# M2k_Breadboard_r1.net
KiCad netlist of a schematic drawn in EAGLE
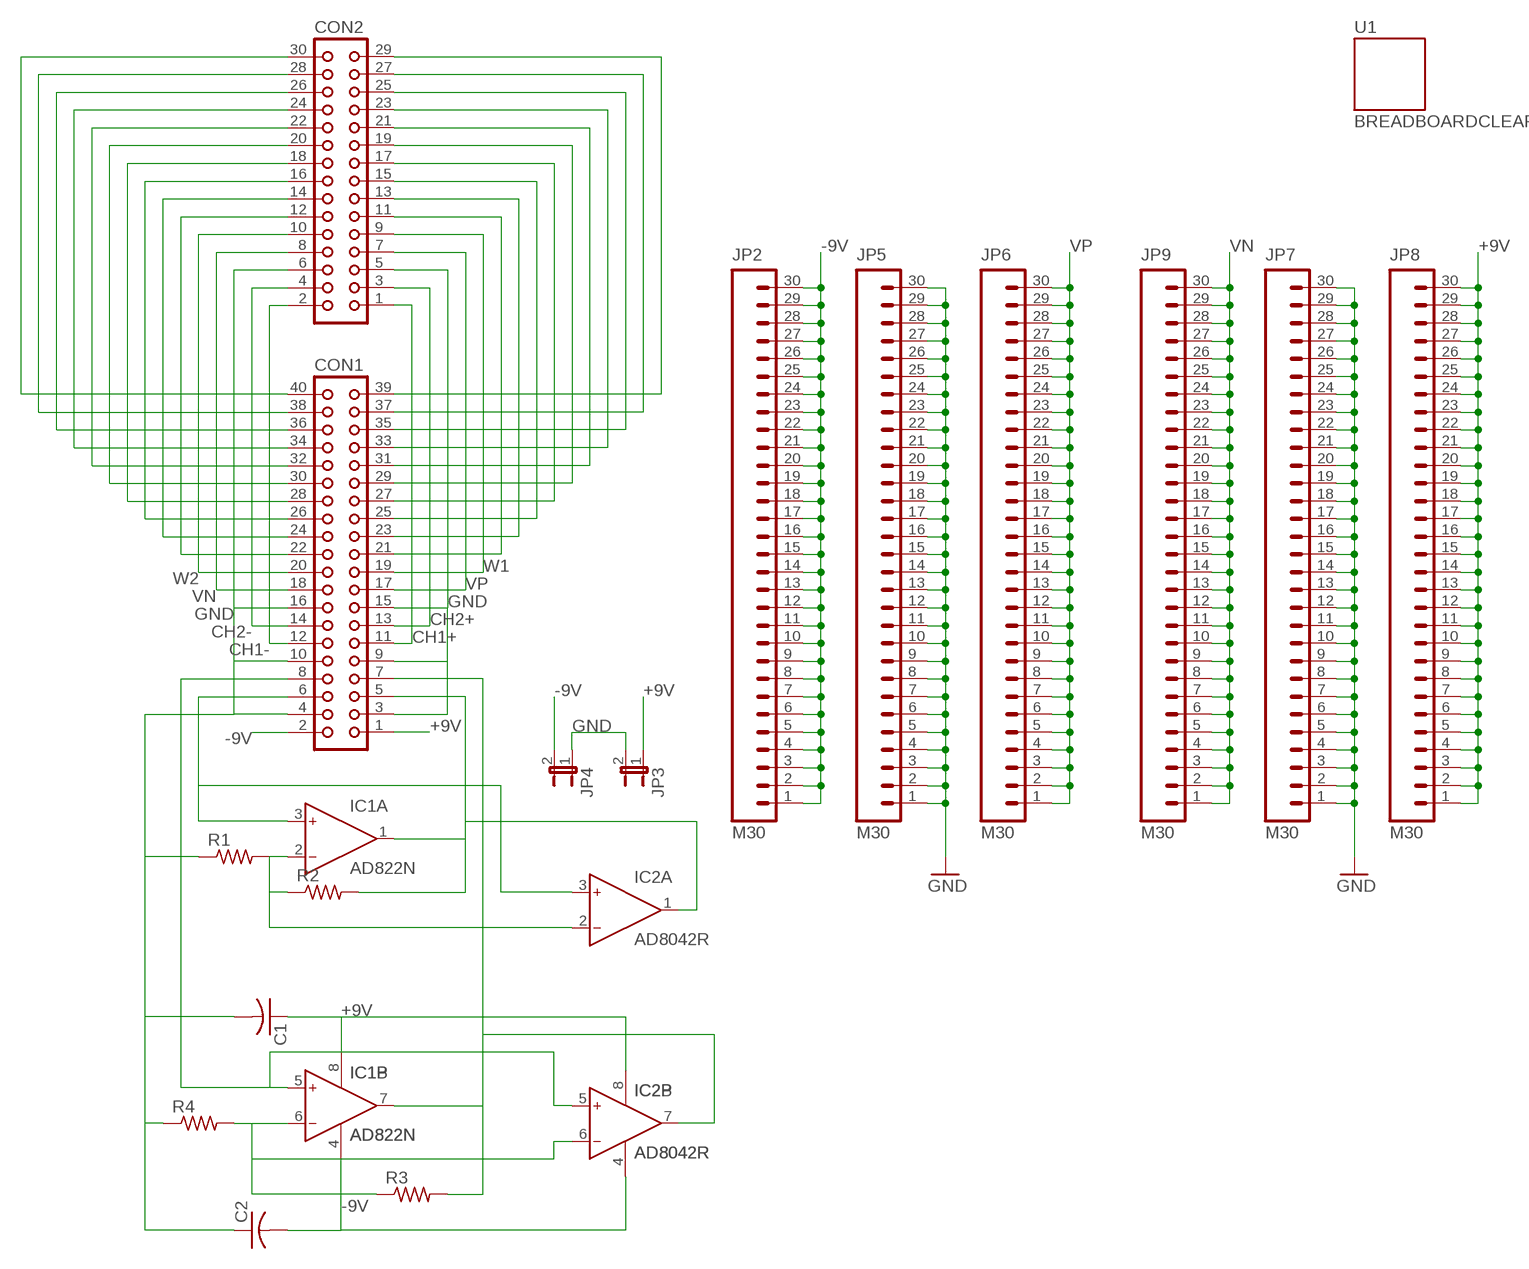
[diagram p0: schematic, sheet 1]

(export (version "E")
  (design (tool "Eeschema 10.0.6"))
  (components
    (comp (ref "C1")
      (value "C-US050-024X044")
      (footprint "eagle-import:C050-024X044")
      (libsource (lib "eagle-import") (part "C-US050-024X044"))
    )
    (comp (ref "C2")
      (value "C-US050-024X044")
      (footprint "eagle-import:C050-024X044")
      (libsource (lib "eagle-import") (part "C-US050-024X044"))
    )
    (comp (ref "CON1")
      (value "CON40")
      (footprint "eagle-import:CON40")
      (libsource (lib "eagle-import") (part "CON40"))
    )
    (comp (ref "CON2")
      (value "CON34")
      (footprint "eagle-import:CON34")
      (libsource (lib "eagle-import") (part "CON34"))
    )
    (comp (ref "IC1")
      (value "AD822N")
      (footprint "eagle-import:DIL08")
      (libsource (lib "eagle-import") (part "AD822N"))
    )
    (comp (ref "IC2")
      (value "AD8042R")
      (footprint "eagle-import:SO8")
      (fields (field (name "MF") "ALTERA CORPORATION") (field (name "MPN") "AD8042AR"))
      (libsource (lib "eagle-import") (part "AD8042R"))
    )
    (comp (ref "JP2")
      (value "M30")
      (footprint "eagle-import:1X30")
      (libsource (lib "eagle-import") (part "M30"))
    )
    (comp (ref "JP3")
      (value "JP1E")
      (footprint "eagle-import:JP1")
      (libsource (lib "eagle-import") (part "JP1E"))
    )
    (comp (ref "JP4")
      (value "JP1E")
      (footprint "eagle-import:JP1")
      (libsource (lib "eagle-import") (part "JP1E"))
    )
    (comp (ref "JP5")
      (value "M30")
      (footprint "eagle-import:1X30")
      (libsource (lib "eagle-import") (part "M30"))
    )
    (comp (ref "JP6")
      (value "M30")
      (footprint "eagle-import:1X30")
      (libsource (lib "eagle-import") (part "M30"))
    )
    (comp (ref "JP7")
      (value "M30")
      (footprint "eagle-import:1X30")
      (libsource (lib "eagle-import") (part "M30"))
    )
    (comp (ref "JP8")
      (value "M30")
      (footprint "eagle-import:1X30")
      (libsource (lib "eagle-import") (part "M30"))
    )
    (comp (ref "JP9")
      (value "M30")
      (footprint "eagle-import:1X30")
      (libsource (lib "eagle-import") (part "M30"))
    )
    (comp (ref "R1")
      (value "R-US_0207/7")
      (footprint "eagle-import:0207_7")
      (libsource (lib "eagle-import") (part "R-US_0207/7"))
    )
    (comp (ref "R2")
      (value "R-US_0207/7")
      (footprint "eagle-import:0207_7")
      (libsource (lib "eagle-import") (part "R-US_0207/7"))
    )
    (comp (ref "R3")
      (value "R-US_0207/7")
      (footprint "eagle-import:0207_7")
      (libsource (lib "eagle-import") (part "R-US_0207/7"))
    )
    (comp (ref "R4")
      (value "R-US_0207/7")
      (footprint "eagle-import:0207_7")
      (libsource (lib "eagle-import") (part "R-US_0207/7"))
    )
    (comp (ref "U1")
      (value "BREADBOARDCLEAR")
      (footprint "eagle-import:BREADBOARD_CLEAR")
      (libsource (lib "eagle-import") (part "BREADBOARDCLEAR"))
    )
  )
  (nets
    (net (code "1") (name "/+9V") (class "Default")
      (node (ref "C1") (pin "1") (pinfunction "1_1") (pintype "passive"))
      (node (ref "CON1") (pin "1") (pinfunction "1_1") (pintype "passive"))
      (node (ref "IC1") (pin "8") (pinfunction "V+_8") (pintype "power_in"))
      (node (ref "IC2") (pin "8") (pinfunction "V+_8") (pintype "power_in"))
      (node (ref "JP3") (pin "1") (pinfunction "1_1") (pintype "passive"))
      (node (ref "JP8") (pin "1") (pinfunction "1_1") (pintype "passive"))
      (node (ref "JP8") (pin "10") (pinfunction "10_10") (pintype "passive"))
      (node (ref "JP8") (pin "11") (pinfunction "11_11") (pintype "passive"))
      (node (ref "JP8") (pin "12") (pinfunction "12_12") (pintype "passive"))
      (node (ref "JP8") (pin "13") (pinfunction "13_13") (pintype "passive"))
      (node (ref "JP8") (pin "14") (pinfunction "14_14") (pintype "passive"))
      (node (ref "JP8") (pin "15") (pinfunction "15_15") (pintype "passive"))
      (node (ref "JP8") (pin "16") (pinfunction "16_16") (pintype "passive"))
      (node (ref "JP8") (pin "17") (pinfunction "17_17") (pintype "passive"))
      (node (ref "JP8") (pin "18") (pinfunction "18_18") (pintype "passive"))
      (node (ref "JP8") (pin "19") (pinfunction "19_19") (pintype "passive"))
      (node (ref "JP8") (pin "2") (pinfunction "2_2") (pintype "passive"))
      (node (ref "JP8") (pin "20") (pinfunction "20_20") (pintype "passive"))
      (node (ref "JP8") (pin "21") (pinfunction "21_21") (pintype "passive"))
      (node (ref "JP8") (pin "22") (pinfunction "22_22") (pintype "passive"))
      (node (ref "JP8") (pin "23") (pinfunction "23_23") (pintype "passive"))
      (node (ref "JP8") (pin "24") (pinfunction "24_24") (pintype "passive"))
      (node (ref "JP8") (pin "25") (pinfunction "25_25") (pintype "passive"))
      (node (ref "JP8") (pin "26") (pinfunction "26_26") (pintype "passive"))
      (node (ref "JP8") (pin "27") (pinfunction "27_27") (pintype "passive"))
      (node (ref "JP8") (pin "28") (pinfunction "28_28") (pintype "passive"))
      (node (ref "JP8") (pin "29") (pinfunction "29_29") (pintype "passive"))
      (node (ref "JP8") (pin "3") (pinfunction "3_3") (pintype "passive"))
      (node (ref "JP8") (pin "30") (pinfunction "30_30") (pintype "passive"))
      (node (ref "JP8") (pin "4") (pinfunction "4_4") (pintype "passive"))
      (node (ref "JP8") (pin "5") (pinfunction "5_5") (pintype "passive"))
      (node (ref "JP8") (pin "6") (pinfunction "6_6") (pintype "passive"))
      (node (ref "JP8") (pin "7") (pinfunction "7_7") (pintype "passive"))
      (node (ref "JP8") (pin "8") (pinfunction "8_8") (pintype "passive"))
      (node (ref "JP8") (pin "9") (pinfunction "9_9") (pintype "passive"))
    )
    (net (code "2") (name "/-9V") (class "Default")
      (node (ref "C2") (pin "2") (pinfunction "2_2") (pintype "passive"))
      (node (ref "CON1") (pin "2") (pinfunction "2_2") (pintype "passive"))
      (node (ref "IC1") (pin "4") (pinfunction "V-_4") (pintype "power_in"))
      (node (ref "IC2") (pin "4") (pinfunction "V-_4") (pintype "power_in"))
      (node (ref "JP2") (pin "1") (pinfunction "1_1") (pintype "passive"))
      (node (ref "JP2") (pin "10") (pinfunction "10_10") (pintype "passive"))
      (node (ref "JP2") (pin "11") (pinfunction "11_11") (pintype "passive"))
      (node (ref "JP2") (pin "12") (pinfunction "12_12") (pintype "passive"))
      (node (ref "JP2") (pin "13") (pinfunction "13_13") (pintype "passive"))
      (node (ref "JP2") (pin "14") (pinfunction "14_14") (pintype "passive"))
      (node (ref "JP2") (pin "15") (pinfunction "15_15") (pintype "passive"))
      (node (ref "JP2") (pin "16") (pinfunction "16_16") (pintype "passive"))
      (node (ref "JP2") (pin "17") (pinfunction "17_17") (pintype "passive"))
      (node (ref "JP2") (pin "18") (pinfunction "18_18") (pintype "passive"))
      (node (ref "JP2") (pin "19") (pinfunction "19_19") (pintype "passive"))
      (node (ref "JP2") (pin "2") (pinfunction "2_2") (pintype "passive"))
      (node (ref "JP2") (pin "20") (pinfunction "20_20") (pintype "passive"))
      (node (ref "JP2") (pin "21") (pinfunction "21_21") (pintype "passive"))
      (node (ref "JP2") (pin "22") (pinfunction "22_22") (pintype "passive"))
      (node (ref "JP2") (pin "23") (pinfunction "23_23") (pintype "passive"))
      (node (ref "JP2") (pin "24") (pinfunction "24_24") (pintype "passive"))
      (node (ref "JP2") (pin "25") (pinfunction "25_25") (pintype "passive"))
      (node (ref "JP2") (pin "26") (pinfunction "26_26") (pintype "passive"))
      (node (ref "JP2") (pin "27") (pinfunction "27_27") (pintype "passive"))
      (node (ref "JP2") (pin "28") (pinfunction "28_28") (pintype "passive"))
      (node (ref "JP2") (pin "29") (pinfunction "29_29") (pintype "passive"))
      (node (ref "JP2") (pin "3") (pinfunction "3_3") (pintype "passive"))
      (node (ref "JP2") (pin "30") (pinfunction "30_30") (pintype "passive"))
      (node (ref "JP2") (pin "4") (pinfunction "4_4") (pintype "passive"))
      (node (ref "JP2") (pin "5") (pinfunction "5_5") (pintype "passive"))
      (node (ref "JP2") (pin "6") (pinfunction "6_6") (pintype "passive"))
      (node (ref "JP2") (pin "7") (pinfunction "7_7") (pintype "passive"))
      (node (ref "JP2") (pin "8") (pinfunction "8_8") (pintype "passive"))
      (node (ref "JP2") (pin "9") (pinfunction "9_9") (pintype "passive"))
      (node (ref "JP4") (pin "2") (pinfunction "2_2") (pintype "passive"))
    )
    (net (code "3") (name "/CH1+") (class "Default")
      (node (ref "CON1") (pin "11") (pinfunction "11_11") (pintype "passive"))
      (node (ref "CON2") (pin "1") (pinfunction "1_1") (pintype "passive"))
    )
    (net (code "4") (name "/CH1-") (class "Default")
      (node (ref "CON1") (pin "12") (pinfunction "12_12") (pintype "passive"))
      (node (ref "CON2") (pin "2") (pinfunction "2_2") (pintype "passive"))
    )
    (net (code "5") (name "/CH2+") (class "Default")
      (node (ref "CON1") (pin "13") (pinfunction "13_13") (pintype "passive"))
      (node (ref "CON2") (pin "3") (pinfunction "3_3") (pintype "passive"))
    )
    (net (code "6") (name "/CH2-") (class "Default")
      (node (ref "CON1") (pin "14") (pinfunction "14_14") (pintype "passive"))
      (node (ref "CON2") (pin "4") (pinfunction "4_4") (pintype "passive"))
    )
    (net (code "7") (name "/VN") (class "Default")
      (node (ref "CON1") (pin "18") (pinfunction "18_18") (pintype "passive"))
      (node (ref "CON2") (pin "8") (pinfunction "8_8") (pintype "passive"))
      (node (ref "JP9") (pin "1") (pinfunction "1_1") (pintype "passive"))
      (node (ref "JP9") (pin "10") (pinfunction "10_10") (pintype "passive"))
      (node (ref "JP9") (pin "11") (pinfunction "11_11") (pintype "passive"))
      (node (ref "JP9") (pin "12") (pinfunction "12_12") (pintype "passive"))
      (node (ref "JP9") (pin "13") (pinfunction "13_13") (pintype "passive"))
      (node (ref "JP9") (pin "14") (pinfunction "14_14") (pintype "passive"))
      (node (ref "JP9") (pin "15") (pinfunction "15_15") (pintype "passive"))
      (node (ref "JP9") (pin "16") (pinfunction "16_16") (pintype "passive"))
      (node (ref "JP9") (pin "17") (pinfunction "17_17") (pintype "passive"))
      (node (ref "JP9") (pin "18") (pinfunction "18_18") (pintype "passive"))
      (node (ref "JP9") (pin "19") (pinfunction "19_19") (pintype "passive"))
      (node (ref "JP9") (pin "2") (pinfunction "2_2") (pintype "passive"))
      (node (ref "JP9") (pin "20") (pinfunction "20_20") (pintype "passive"))
      (node (ref "JP9") (pin "21") (pinfunction "21_21") (pintype "passive"))
      (node (ref "JP9") (pin "22") (pinfunction "22_22") (pintype "passive"))
      (node (ref "JP9") (pin "23") (pinfunction "23_23") (pintype "passive"))
      (node (ref "JP9") (pin "24") (pinfunction "24_24") (pintype "passive"))
      (node (ref "JP9") (pin "25") (pinfunction "25_25") (pintype "passive"))
      (node (ref "JP9") (pin "26") (pinfunction "26_26") (pintype "passive"))
      (node (ref "JP9") (pin "27") (pinfunction "27_27") (pintype "passive"))
      (node (ref "JP9") (pin "28") (pinfunction "28_28") (pintype "passive"))
      (node (ref "JP9") (pin "29") (pinfunction "29_29") (pintype "passive"))
      (node (ref "JP9") (pin "3") (pinfunction "3_3") (pintype "passive"))
      (node (ref "JP9") (pin "30") (pinfunction "30_30") (pintype "passive"))
      (node (ref "JP9") (pin "4") (pinfunction "4_4") (pintype "passive"))
      (node (ref "JP9") (pin "5") (pinfunction "5_5") (pintype "passive"))
      (node (ref "JP9") (pin "6") (pinfunction "6_6") (pintype "passive"))
      (node (ref "JP9") (pin "7") (pinfunction "7_7") (pintype "passive"))
      (node (ref "JP9") (pin "8") (pinfunction "8_8") (pintype "passive"))
      (node (ref "JP9") (pin "9") (pinfunction "9_9") (pintype "passive"))
    )
    (net (code "8") (name "/VP") (class "Default")
      (node (ref "CON1") (pin "17") (pinfunction "17_17") (pintype "passive"))
      (node (ref "CON2") (pin "7") (pinfunction "7_7") (pintype "passive"))
      (node (ref "JP6") (pin "1") (pinfunction "1_1") (pintype "passive"))
      (node (ref "JP6") (pin "10") (pinfunction "10_10") (pintype "passive"))
      (node (ref "JP6") (pin "11") (pinfunction "11_11") (pintype "passive"))
      (node (ref "JP6") (pin "12") (pinfunction "12_12") (pintype "passive"))
      (node (ref "JP6") (pin "13") (pinfunction "13_13") (pintype "passive"))
      (node (ref "JP6") (pin "14") (pinfunction "14_14") (pintype "passive"))
      (node (ref "JP6") (pin "15") (pinfunction "15_15") (pintype "passive"))
      (node (ref "JP6") (pin "16") (pinfunction "16_16") (pintype "passive"))
      (node (ref "JP6") (pin "17") (pinfunction "17_17") (pintype "passive"))
      (node (ref "JP6") (pin "18") (pinfunction "18_18") (pintype "passive"))
      (node (ref "JP6") (pin "19") (pinfunction "19_19") (pintype "passive"))
      (node (ref "JP6") (pin "2") (pinfunction "2_2") (pintype "passive"))
      (node (ref "JP6") (pin "20") (pinfunction "20_20") (pintype "passive"))
      (node (ref "JP6") (pin "21") (pinfunction "21_21") (pintype "passive"))
      (node (ref "JP6") (pin "22") (pinfunction "22_22") (pintype "passive"))
      (node (ref "JP6") (pin "23") (pinfunction "23_23") (pintype "passive"))
      (node (ref "JP6") (pin "24") (pinfunction "24_24") (pintype "passive"))
      (node (ref "JP6") (pin "25") (pinfunction "25_25") (pintype "passive"))
      (node (ref "JP6") (pin "26") (pinfunction "26_26") (pintype "passive"))
      (node (ref "JP6") (pin "27") (pinfunction "27_27") (pintype "passive"))
      (node (ref "JP6") (pin "28") (pinfunction "28_28") (pintype "passive"))
      (node (ref "JP6") (pin "29") (pinfunction "29_29") (pintype "passive"))
      (node (ref "JP6") (pin "3") (pinfunction "3_3") (pintype "passive"))
      (node (ref "JP6") (pin "30") (pinfunction "30_30") (pintype "passive"))
      (node (ref "JP6") (pin "4") (pinfunction "4_4") (pintype "passive"))
      (node (ref "JP6") (pin "5") (pinfunction "5_5") (pintype "passive"))
      (node (ref "JP6") (pin "6") (pinfunction "6_6") (pintype "passive"))
      (node (ref "JP6") (pin "7") (pinfunction "7_7") (pintype "passive"))
      (node (ref "JP6") (pin "8") (pinfunction "8_8") (pintype "passive"))
      (node (ref "JP6") (pin "9") (pinfunction "9_9") (pintype "passive"))
    )
    (net (code "9") (name "/W1") (class "Default")
      (node (ref "CON1") (pin "19") (pinfunction "19_19") (pintype "passive"))
      (node (ref "CON2") (pin "9") (pinfunction "9_9") (pintype "passive"))
    )
    (net (code "10") (name "/W2") (class "Default")
      (node (ref "CON1") (pin "20") (pinfunction "20_20") (pintype "passive"))
      (node (ref "CON2") (pin "10") (pinfunction "10_10") (pintype "passive"))
    )
    (net (code "11") (name "GND") (class "Default")
      (node (ref "C1") (pin "2") (pinfunction "2_2") (pintype "passive"))
      (node (ref "C2") (pin "1") (pinfunction "1_1") (pintype "passive"))
      (node (ref "CON1") (pin "10") (pinfunction "10_10") (pintype "passive"))
      (node (ref "CON1") (pin "15") (pinfunction "15_15") (pintype "passive"))
      (node (ref "CON1") (pin "16") (pinfunction "16_16") (pintype "passive"))
      (node (ref "CON1") (pin "3") (pinfunction "3_3") (pintype "passive"))
      (node (ref "CON1") (pin "4") (pinfunction "4_4") (pintype "passive"))
      (node (ref "CON1") (pin "9") (pinfunction "9_9") (pintype "passive"))
      (node (ref "CON2") (pin "5") (pinfunction "5_5") (pintype "passive"))
      (node (ref "CON2") (pin "6") (pinfunction "6_6") (pintype "passive"))
      (node (ref "JP3") (pin "2") (pinfunction "2_2") (pintype "passive"))
      (node (ref "JP4") (pin "1") (pinfunction "1_1") (pintype "passive"))
      (node (ref "JP5") (pin "1") (pinfunction "1_1") (pintype "passive"))
      (node (ref "JP5") (pin "10") (pinfunction "10_10") (pintype "passive"))
      (node (ref "JP5") (pin "11") (pinfunction "11_11") (pintype "passive"))
      (node (ref "JP5") (pin "12") (pinfunction "12_12") (pintype "passive"))
      (node (ref "JP5") (pin "13") (pinfunction "13_13") (pintype "passive"))
      (node (ref "JP5") (pin "14") (pinfunction "14_14") (pintype "passive"))
      (node (ref "JP5") (pin "15") (pinfunction "15_15") (pintype "passive"))
      (node (ref "JP5") (pin "16") (pinfunction "16_16") (pintype "passive"))
      (node (ref "JP5") (pin "17") (pinfunction "17_17") (pintype "passive"))
      (node (ref "JP5") (pin "18") (pinfunction "18_18") (pintype "passive"))
      (node (ref "JP5") (pin "19") (pinfunction "19_19") (pintype "passive"))
      (node (ref "JP5") (pin "2") (pinfunction "2_2") (pintype "passive"))
      (node (ref "JP5") (pin "20") (pinfunction "20_20") (pintype "passive"))
      (node (ref "JP5") (pin "21") (pinfunction "21_21") (pintype "passive"))
      (node (ref "JP5") (pin "22") (pinfunction "22_22") (pintype "passive"))
      (node (ref "JP5") (pin "23") (pinfunction "23_23") (pintype "passive"))
      (node (ref "JP5") (pin "24") (pinfunction "24_24") (pintype "passive"))
      (node (ref "JP5") (pin "25") (pinfunction "25_25") (pintype "passive"))
      (node (ref "JP5") (pin "26") (pinfunction "26_26") (pintype "passive"))
      (node (ref "JP5") (pin "27") (pinfunction "27_27") (pintype "passive"))
      (node (ref "JP5") (pin "28") (pinfunction "28_28") (pintype "passive"))
      (node (ref "JP5") (pin "29") (pinfunction "29_29") (pintype "passive"))
      (node (ref "JP5") (pin "3") (pinfunction "3_3") (pintype "passive"))
      (node (ref "JP5") (pin "30") (pinfunction "30_30") (pintype "passive"))
      (node (ref "JP5") (pin "4") (pinfunction "4_4") (pintype "passive"))
      (node (ref "JP5") (pin "5") (pinfunction "5_5") (pintype "passive"))
      (node (ref "JP5") (pin "6") (pinfunction "6_6") (pintype "passive"))
      (node (ref "JP5") (pin "7") (pinfunction "7_7") (pintype "passive"))
      (node (ref "JP5") (pin "8") (pinfunction "8_8") (pintype "passive"))
      (node (ref "JP5") (pin "9") (pinfunction "9_9") (pintype "passive"))
      (node (ref "JP7") (pin "1") (pinfunction "1_1") (pintype "passive"))
      (node (ref "JP7") (pin "10") (pinfunction "10_10") (pintype "passive"))
      (node (ref "JP7") (pin "11") (pinfunction "11_11") (pintype "passive"))
      (node (ref "JP7") (pin "12") (pinfunction "12_12") (pintype "passive"))
      (node (ref "JP7") (pin "13") (pinfunction "13_13") (pintype "passive"))
      (node (ref "JP7") (pin "14") (pinfunction "14_14") (pintype "passive"))
      (node (ref "JP7") (pin "15") (pinfunction "15_15") (pintype "passive"))
      (node (ref "JP7") (pin "16") (pinfunction "16_16") (pintype "passive"))
      (node (ref "JP7") (pin "17") (pinfunction "17_17") (pintype "passive"))
      (node (ref "JP7") (pin "18") (pinfunction "18_18") (pintype "passive"))
      (node (ref "JP7") (pin "19") (pinfunction "19_19") (pintype "passive"))
      (node (ref "JP7") (pin "2") (pinfunction "2_2") (pintype "passive"))
      (node (ref "JP7") (pin "20") (pinfunction "20_20") (pintype "passive"))
      (node (ref "JP7") (pin "21") (pinfunction "21_21") (pintype "passive"))
      (node (ref "JP7") (pin "22") (pinfunction "22_22") (pintype "passive"))
      (node (ref "JP7") (pin "23") (pinfunction "23_23") (pintype "passive"))
      (node (ref "JP7") (pin "24") (pinfunction "24_24") (pintype "passive"))
      (node (ref "JP7") (pin "25") (pinfunction "25_25") (pintype "passive"))
      (node (ref "JP7") (pin "26") (pinfunction "26_26") (pintype "passive"))
      (node (ref "JP7") (pin "27") (pinfunction "27_27") (pintype "passive"))
      (node (ref "JP7") (pin "28") (pinfunction "28_28") (pintype "passive"))
      (node (ref "JP7") (pin "29") (pinfunction "29_29") (pintype "passive"))
      (node (ref "JP7") (pin "3") (pinfunction "3_3") (pintype "passive"))
      (node (ref "JP7") (pin "30") (pinfunction "30_30") (pintype "passive"))
      (node (ref "JP7") (pin "4") (pinfunction "4_4") (pintype "passive"))
      (node (ref "JP7") (pin "5") (pinfunction "5_5") (pintype "passive"))
      (node (ref "JP7") (pin "6") (pinfunction "6_6") (pintype "passive"))
      (node (ref "JP7") (pin "7") (pinfunction "7_7") (pintype "passive"))
      (node (ref "JP7") (pin "8") (pinfunction "8_8") (pintype "passive"))
      (node (ref "JP7") (pin "9") (pinfunction "9_9") (pintype "passive"))
      (node (ref "R1") (pin "1") (pinfunction "1_1") (pintype "passive"))
      (node (ref "R4") (pin "1") (pinfunction "1_1") (pintype "passive"))
    )
    (net (code "12") (name "Net-(CON1-Pad21)") (class "Default")
      (node (ref "CON1") (pin "21") (pinfunction "21_21") (pintype "passive"))
      (node (ref "CON2") (pin "11") (pinfunction "11_11") (pintype "passive"))
    )
    (net (code "13") (name "Net-(CON1-Pad22)") (class "Default")
      (node (ref "CON1") (pin "22") (pinfunction "22_22") (pintype "passive"))
      (node (ref "CON2") (pin "12") (pinfunction "12_12") (pintype "passive"))
    )
    (net (code "14") (name "Net-(CON1-Pad23)") (class "Default")
      (node (ref "CON1") (pin "23") (pinfunction "23_23") (pintype "passive"))
      (node (ref "CON2") (pin "13") (pinfunction "13_13") (pintype "passive"))
    )
    (net (code "15") (name "Net-(CON1-Pad24)") (class "Default")
      (node (ref "CON1") (pin "24") (pinfunction "24_24") (pintype "passive"))
      (node (ref "CON2") (pin "14") (pinfunction "14_14") (pintype "passive"))
    )
    (net (code "16") (name "Net-(CON1-Pad25)") (class "Default")
      (node (ref "CON1") (pin "25") (pinfunction "25_25") (pintype "passive"))
      (node (ref "CON2") (pin "15") (pinfunction "15_15") (pintype "passive"))
    )
    (net (code "17") (name "Net-(CON1-Pad26)") (class "Default")
      (node (ref "CON1") (pin "26") (pinfunction "26_26") (pintype "passive"))
      (node (ref "CON2") (pin "16") (pinfunction "16_16") (pintype "passive"))
    )
    (net (code "18") (name "Net-(CON1-Pad27)") (class "Default")
      (node (ref "CON1") (pin "27") (pinfunction "27_27") (pintype "passive"))
      (node (ref "CON2") (pin "17") (pinfunction "17_17") (pintype "passive"))
    )
    (net (code "19") (name "Net-(CON1-Pad28)") (class "Default")
      (node (ref "CON1") (pin "28") (pinfunction "28_28") (pintype "passive"))
      (node (ref "CON2") (pin "18") (pinfunction "18_18") (pintype "passive"))
    )
    (net (code "20") (name "Net-(CON1-Pad29)") (class "Default")
      (node (ref "CON1") (pin "29") (pinfunction "29_29") (pintype "passive"))
      (node (ref "CON2") (pin "19") (pinfunction "19_19") (pintype "passive"))
    )
    (net (code "21") (name "Net-(CON1-Pad30)") (class "Default")
      (node (ref "CON1") (pin "30") (pinfunction "30_30") (pintype "passive"))
      (node (ref "CON2") (pin "20") (pinfunction "20_20") (pintype "passive"))
    )
    (net (code "22") (name "Net-(CON1-Pad31)") (class "Default")
      (node (ref "CON1") (pin "31") (pinfunction "31_31") (pintype "passive"))
      (node (ref "CON2") (pin "21") (pinfunction "21_21") (pintype "passive"))
    )
    (net (code "23") (name "Net-(CON1-Pad32)") (class "Default")
      (node (ref "CON1") (pin "32") (pinfunction "32_32") (pintype "passive"))
      (node (ref "CON2") (pin "22") (pinfunction "22_22") (pintype "passive"))
    )
    (net (code "24") (name "Net-(CON1-Pad33)") (class "Default")
      (node (ref "CON1") (pin "33") (pinfunction "33_33") (pintype "passive"))
      (node (ref "CON2") (pin "23") (pinfunction "23_23") (pintype "passive"))
    )
    (net (code "25") (name "Net-(CON1-Pad34)") (class "Default")
      (node (ref "CON1") (pin "34") (pinfunction "34_34") (pintype "passive"))
      (node (ref "CON2") (pin "24") (pinfunction "24_24") (pintype "passive"))
    )
    (net (code "26") (name "Net-(CON1-Pad35)") (class "Default")
      (node (ref "CON1") (pin "35") (pinfunction "35_35") (pintype "passive"))
      (node (ref "CON2") (pin "25") (pinfunction "25_25") (pintype "passive"))
    )
    (net (code "27") (name "Net-(CON1-Pad36)") (class "Default")
      (node (ref "CON1") (pin "36") (pinfunction "36_36") (pintype "passive"))
      (node (ref "CON2") (pin "26") (pinfunction "26_26") (pintype "passive"))
    )
    (net (code "28") (name "Net-(CON1-Pad37)") (class "Default")
      (node (ref "CON1") (pin "37") (pinfunction "37_37") (pintype "passive"))
      (node (ref "CON2") (pin "27") (pinfunction "27_27") (pintype "passive"))
    )
    (net (code "29") (name "Net-(CON1-Pad38)") (class "Default")
      (node (ref "CON1") (pin "38") (pinfunction "38_38") (pintype "passive"))
      (node (ref "CON2") (pin "28") (pinfunction "28_28") (pintype "passive"))
    )
    (net (code "30") (name "Net-(CON1-Pad39)") (class "Default")
      (node (ref "CON1") (pin "39") (pinfunction "39_39") (pintype "passive"))
      (node (ref "CON2") (pin "29") (pinfunction "29_29") (pintype "passive"))
    )
    (net (code "31") (name "Net-(CON1-Pad40)") (class "Default")
      (node (ref "CON1") (pin "40") (pinfunction "40_40") (pintype "passive"))
      (node (ref "CON2") (pin "30") (pinfunction "30_30") (pintype "passive"))
    )
    (net (code "32") (name "Net-(IC1A-IN+)") (class "Default")
      (node (ref "CON1") (pin "6") (pinfunction "6_6") (pintype "passive"))
      (node (ref "IC1") (pin "3") (pinfunction "IN+_3") (pintype "input"))
      (node (ref "IC2") (pin "3") (pinfunction "IN+_3") (pintype "input"))
    )
    (net (code "33") (name "Net-(IC1A-IN-)") (class "Default")
      (node (ref "IC1") (pin "2") (pinfunction "IN-_2") (pintype "input"))
      (node (ref "IC2") (pin "2") (pinfunction "IN-_2") (pintype "input"))
      (node (ref "R1") (pin "2") (pinfunction "2_2") (pintype "passive"))
      (node (ref "R2") (pin "1") (pinfunction "1_1") (pintype "passive"))
    )
    (net (code "34") (name "Net-(IC1A-OUT)") (class "Default")
      (node (ref "CON1") (pin "5") (pinfunction "5_5") (pintype "passive"))
      (node (ref "IC1") (pin "1") (pinfunction "OUT_1") (pintype "output"))
      (node (ref "IC2") (pin "1") (pinfunction "OUT_1") (pintype "output"))
      (node (ref "R2") (pin "2") (pinfunction "2_2") (pintype "passive"))
    )
    (net (code "35") (name "Net-(IC1B-IN+)") (class "Default")
      (node (ref "CON1") (pin "8") (pinfunction "8_8") (pintype "passive"))
      (node (ref "IC1") (pin "5") (pinfunction "IN+_5") (pintype "input"))
      (node (ref "IC2") (pin "5") (pinfunction "IN+_5") (pintype "input"))
    )
    (net (code "36") (name "Net-(IC1B-IN-)") (class "Default")
      (node (ref "IC1") (pin "6") (pinfunction "IN-_6") (pintype "input"))
      (node (ref "IC2") (pin "6") (pinfunction "IN-_6") (pintype "input"))
      (node (ref "R3") (pin "1") (pinfunction "1_1") (pintype "passive"))
      (node (ref "R4") (pin "2") (pinfunction "2_2") (pintype "passive"))
    )
    (net (code "37") (name "Net-(IC1B-OUT)") (class "Default")
      (node (ref "CON1") (pin "7") (pinfunction "7_7") (pintype "passive"))
      (node (ref "IC1") (pin "7") (pinfunction "OUT_7") (pintype "output"))
      (node (ref "IC2") (pin "7") (pinfunction "OUT_7") (pintype "output"))
      (node (ref "R3") (pin "2") (pinfunction "2_2") (pintype "passive"))
    )
  )
)
